# PowerController.net
KiCad netlist of a schematic drawn in EAGLE
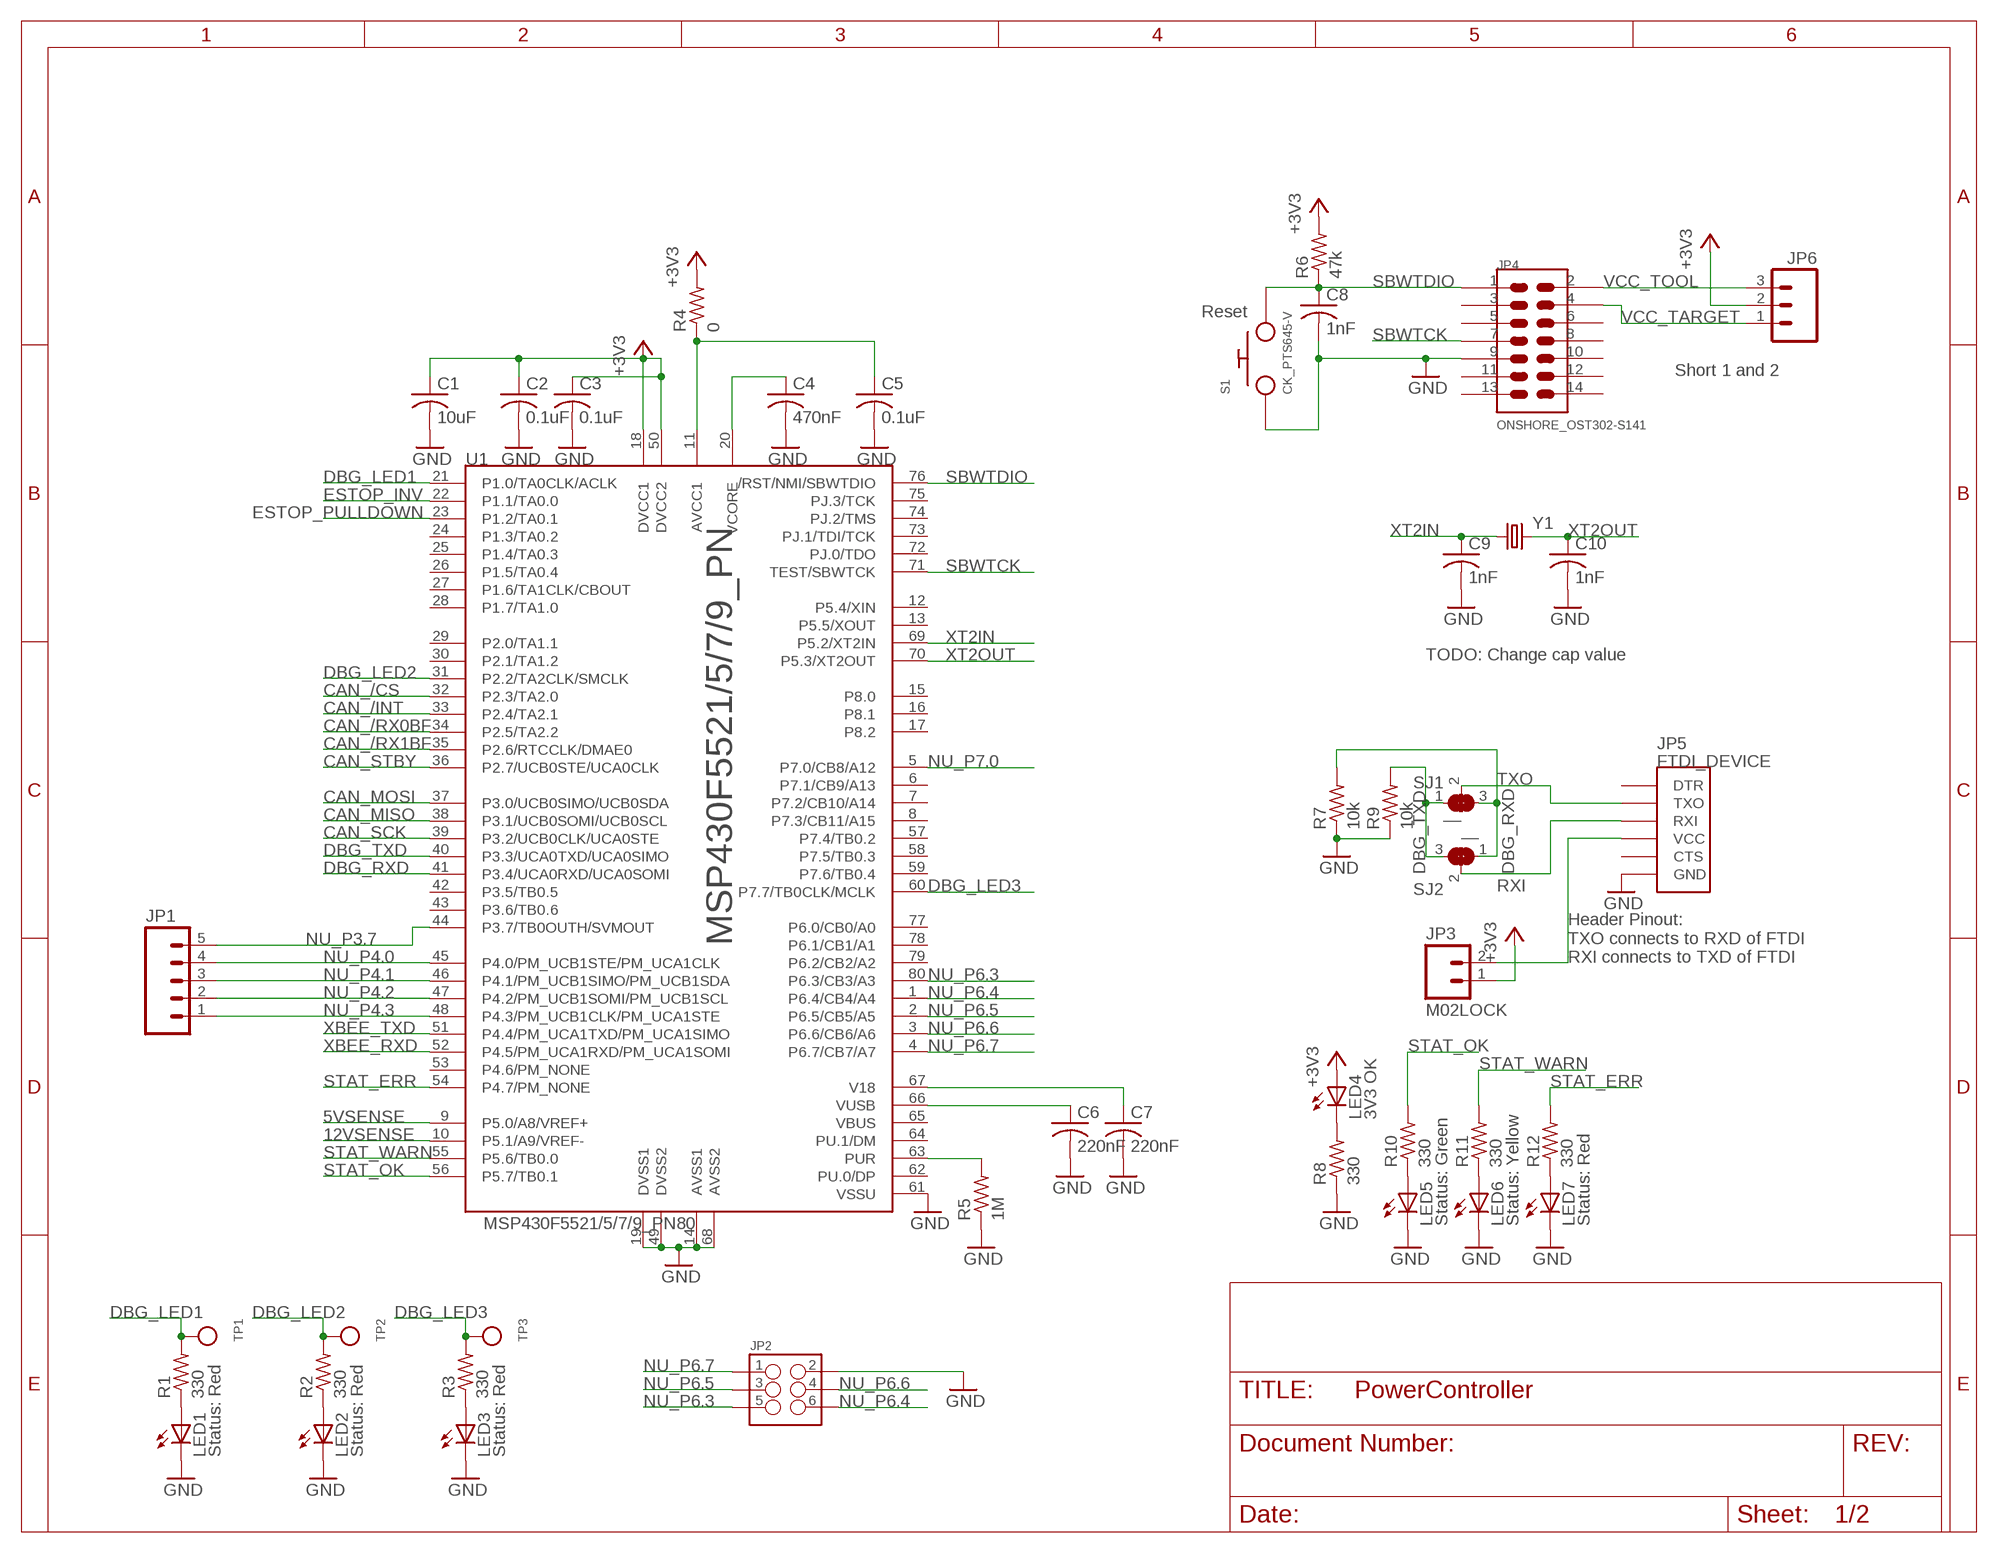
[diagram p0: schematic, sheet 1]
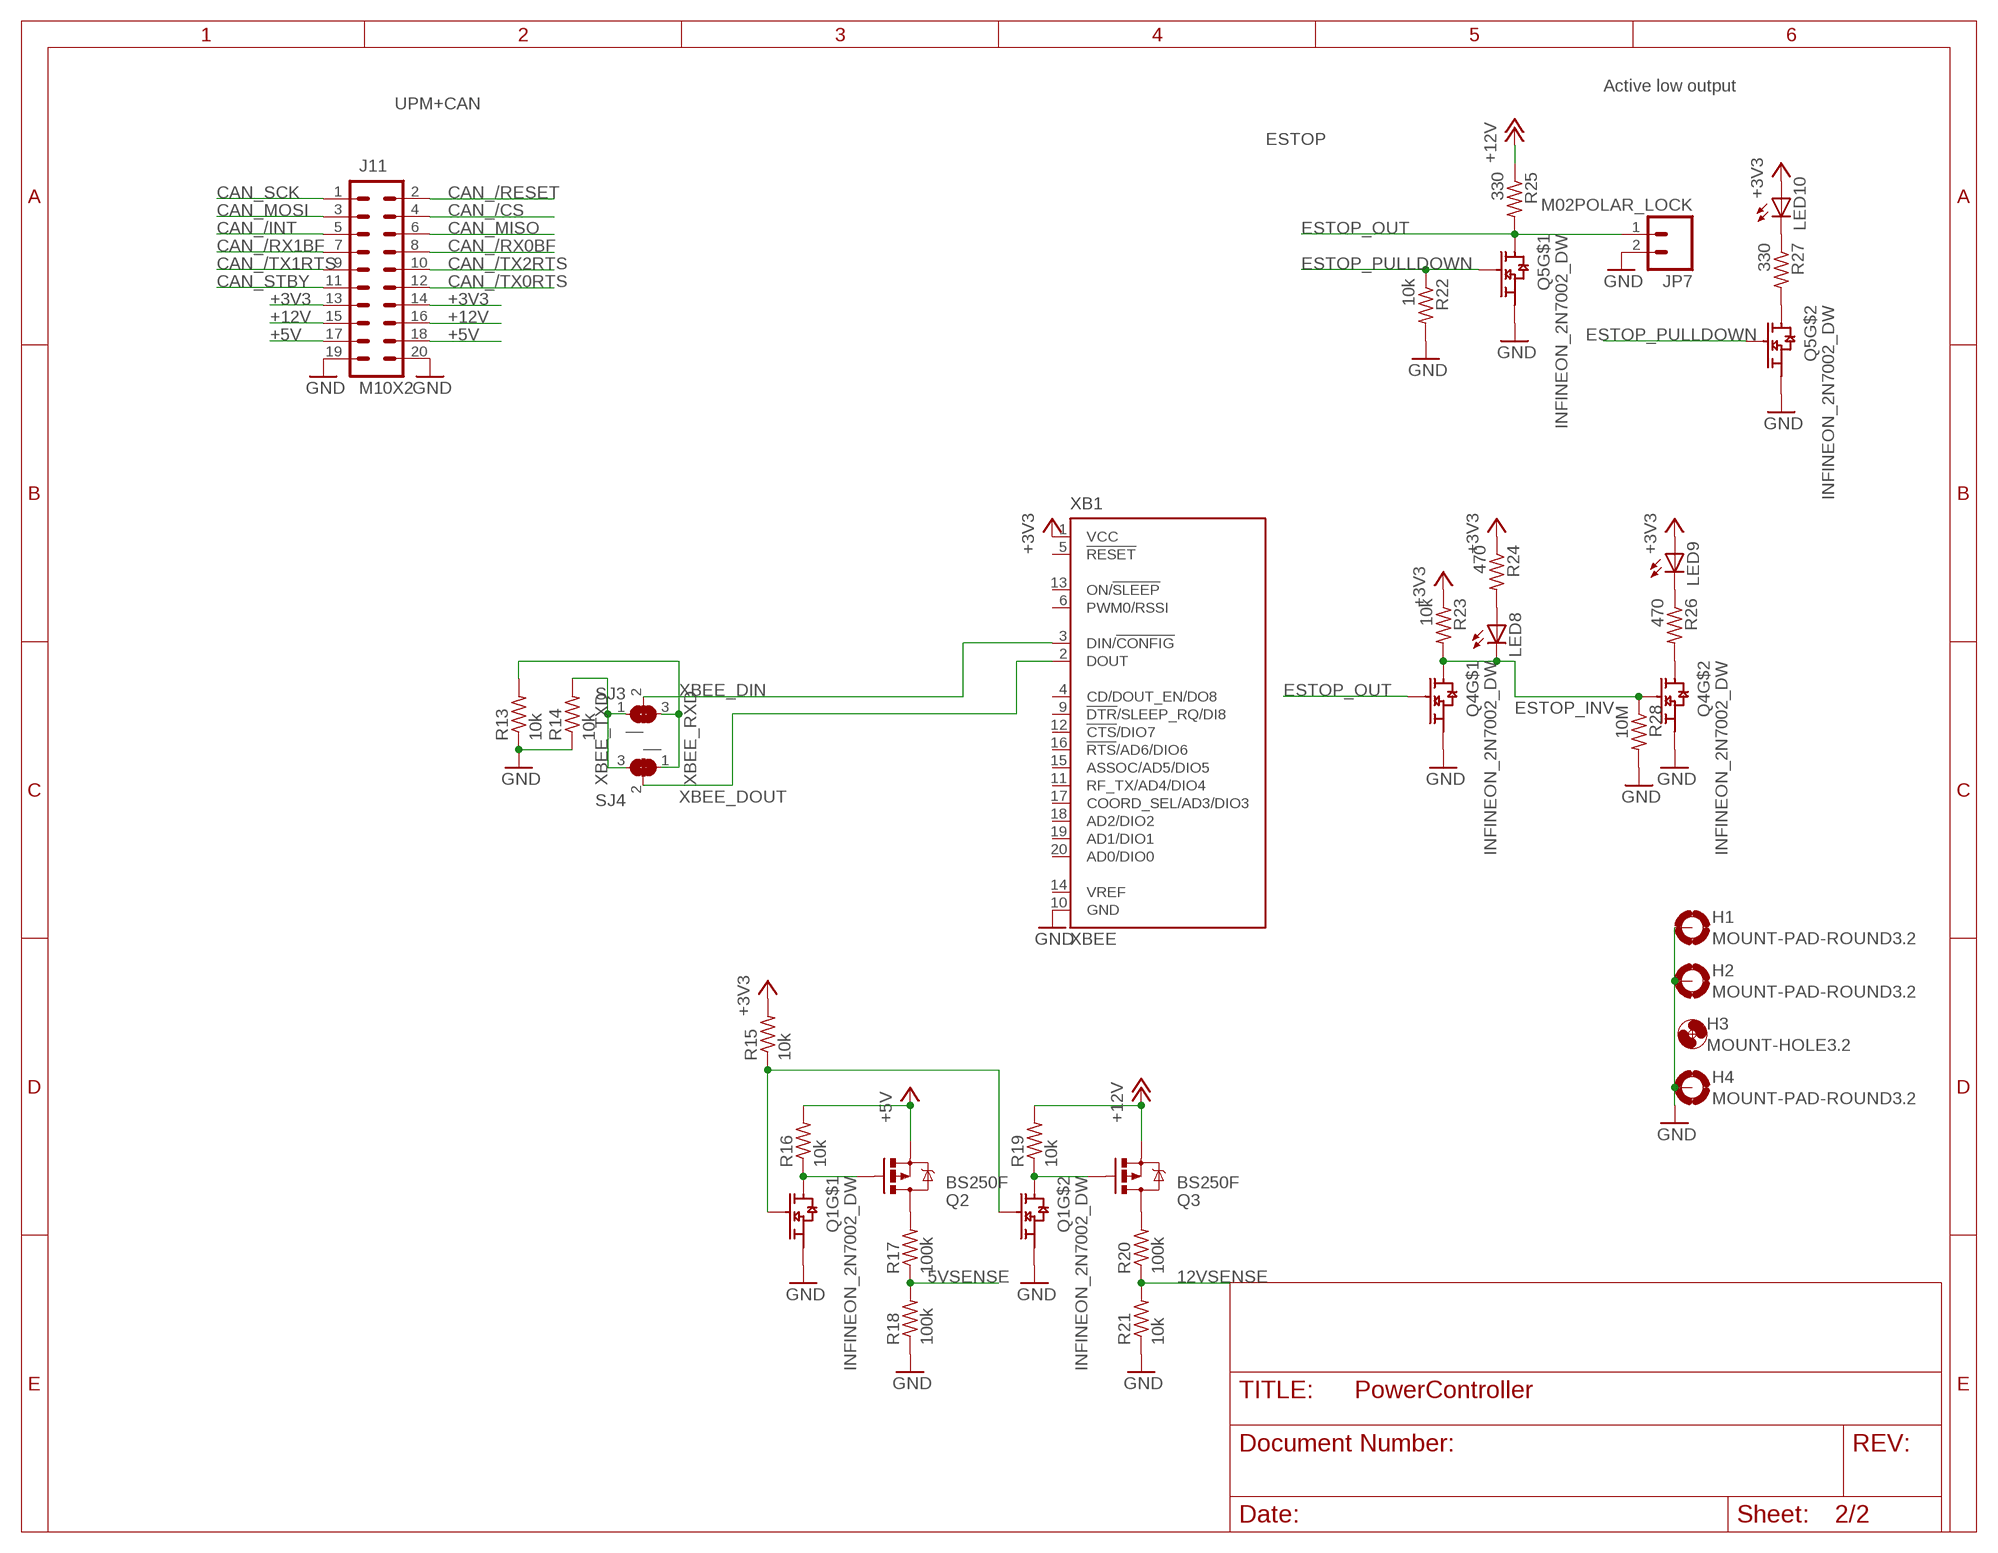
[diagram p1: schematic, sheet 2]

(export (version "E")
  (design (tool "Eeschema 10.0.6"))
  (components
    (comp (ref "H1")
      (value "MOUNT-PAD-ROUND3.2")
      (footprint "eagle-import:3,2-PAD")
      (libsource (lib "eagle-import") (part "MOUNT-PAD-ROUND3.2"))
    )
    (comp (ref "H2")
      (value "MOUNT-PAD-ROUND3.2")
      (footprint "eagle-import:3,2-PAD")
      (libsource (lib "eagle-import") (part "MOUNT-PAD-ROUND3.2"))
    )
    (comp (ref "H3")
      (value "MOUNT-HOLE3.2")
      (footprint "eagle-import:3,2")
      (libsource (lib "eagle-import") (part "MOUNT-HOLE3.2"))
    )
    (comp (ref "H4")
      (value "MOUNT-PAD-ROUND3.2")
      (footprint "eagle-import:3,2-PAD")
      (libsource (lib "eagle-import") (part "MOUNT-PAD-ROUND3.2"))
    )
    (comp (ref "J11")
      (value "M10X2")
      (footprint "eagle-import:2X10")
      (libsource (lib "eagle-import") (part "M10X2"))
    )
    (comp (ref "JP7")
      (value "M02POLAR_LOCK")
      (footprint "eagle-import:MOLEX-1X2_LOCK")
      (libsource (lib "eagle-import") (part "M02POLAR_LOCK"))
    )
    (comp (ref "LED8")
      (value "LED0603")
      (footprint "eagle-import:LED-0603")
      (libsource (lib "eagle-import") (part "LED0603"))
    )
    (comp (ref "LED9")
      (value "LED0603")
      (footprint "eagle-import:LED-0603")
      (libsource (lib "eagle-import") (part "LED0603"))
    )
    (comp (ref "LED10")
      (value "LED0603")
      (footprint "eagle-import:LED-0603")
      (libsource (lib "eagle-import") (part "LED0603"))
    )
    (comp (ref "Q1")
      (value "INFINEON_2N7002_DW")
      (footprint "eagle-import:INFINEON_SOT363")
      (libsource (lib "eagle-import") (part "INFINEON_2N7002_DW"))
    )
    (comp (ref "Q2")
      (value "BS250F")
      (footprint "eagle-import:SOT23-3")
      (libsource (lib "eagle-import") (part "MOSFET-PCHANNELSMD"))
    )
    (comp (ref "Q3")
      (value "BS250F")
      (footprint "eagle-import:SOT23-3")
      (libsource (lib "eagle-import") (part "MOSFET-PCHANNELSMD"))
    )
    (comp (ref "Q4")
      (value "INFINEON_2N7002_DW")
      (footprint "eagle-import:INFINEON_SOT363")
      (libsource (lib "eagle-import") (part "INFINEON_2N7002_DW"))
    )
    (comp (ref "Q5")
      (value "INFINEON_2N7002_DW")
      (footprint "eagle-import:INFINEON_SOT363")
      (libsource (lib "eagle-import") (part "INFINEON_2N7002_DW"))
    )
    (comp (ref "R13")
      (value "10k")
      (footprint "eagle-import:R0603")
      (libsource (lib "eagle-import") (part "R-US_R0603"))
    )
    (comp (ref "R14")
      (value "10k")
      (footprint "eagle-import:R0603")
      (libsource (lib "eagle-import") (part "R-US_R0603"))
    )
    (comp (ref "R15")
      (value "10k")
      (footprint "eagle-import:R0603")
      (libsource (lib "eagle-import") (part "R-US_R0603"))
    )
    (comp (ref "R16")
      (value "10k")
      (footprint "eagle-import:R0603")
      (libsource (lib "eagle-import") (part "R-US_R0603"))
    )
    (comp (ref "R17")
      (value "100k")
      (footprint "eagle-import:R0603")
      (libsource (lib "eagle-import") (part "R-US_R0603"))
    )
    (comp (ref "R18")
      (value "100k")
      (footprint "eagle-import:R0603")
      (libsource (lib "eagle-import") (part "R-US_R0603"))
    )
    (comp (ref "R19")
      (value "10k")
      (footprint "eagle-import:R0603")
      (libsource (lib "eagle-import") (part "R-US_R0603"))
    )
    (comp (ref "R20")
      (value "100k")
      (footprint "eagle-import:R0603")
      (libsource (lib "eagle-import") (part "R-US_R0603"))
    )
    (comp (ref "R21")
      (value "10k")
      (footprint "eagle-import:R0603")
      (libsource (lib "eagle-import") (part "R-US_R0603"))
    )
    (comp (ref "R22")
      (value "10k")
      (footprint "eagle-import:R0603")
      (libsource (lib "eagle-import") (part "R-US_R0603"))
    )
    (comp (ref "R23")
      (value "10k")
      (footprint "eagle-import:R0603")
      (libsource (lib "eagle-import") (part "R-US_R0603"))
    )
    (comp (ref "R24")
      (value "470")
      (footprint "eagle-import:R0603")
      (libsource (lib "eagle-import") (part "R-US_R0603"))
    )
    (comp (ref "R25")
      (value "330")
      (footprint "eagle-import:R0603")
      (libsource (lib "eagle-import") (part "R-US_R0603"))
    )
    (comp (ref "R26")
      (value "470")
      (footprint "eagle-import:R0603")
      (libsource (lib "eagle-import") (part "R-US_R0603"))
    )
    (comp (ref "R27")
      (value "330")
      (footprint "eagle-import:R0603")
      (libsource (lib "eagle-import") (part "R-US_R0603"))
    )
    (comp (ref "R28")
      (value "10M")
      (footprint "eagle-import:R0603")
      (libsource (lib "eagle-import") (part "R-US_R0603"))
    )
    (comp (ref "SJ3")
      (value "SOLDERJUMPER_2WAY0603")
      (footprint "eagle-import:SOLDERJUMPER_2WAY_OPEN_0603")
      (libsource (lib "eagle-import") (part "SOLDERJUMPER_2WAY0603"))
    )
    (comp (ref "SJ4")
      (value "SOLDERJUMPER_2WAY0603")
      (footprint "eagle-import:SOLDERJUMPER_2WAY_OPEN_0603")
      (libsource (lib "eagle-import") (part "SOLDERJUMPER_2WAY0603"))
    )
    (comp (ref "XB1")
      (value "XBEE")
      (footprint "eagle-import:XBEE")
      (libsource (lib "eagle-import") (part "XBEE"))
    )
    (comp (ref "C1")
      (value "10uF")
      (footprint "eagle-import:C0805")
      (libsource (lib "eagle-import") (part "C-USC0805"))
    )
    (comp (ref "C2")
      (value "0.1uF")
      (footprint "eagle-import:C0603")
      (libsource (lib "eagle-import") (part "C-USC0603"))
    )
    (comp (ref "C3")
      (value "0.1uF")
      (footprint "eagle-import:C0603")
      (libsource (lib "eagle-import") (part "C-USC0603"))
    )
    (comp (ref "C4")
      (value "470nF")
      (footprint "eagle-import:C0603")
      (libsource (lib "eagle-import") (part "C-USC0603"))
    )
    (comp (ref "C5")
      (value "0.1uF")
      (footprint "eagle-import:C0603")
      (libsource (lib "eagle-import") (part "C-USC0603"))
    )
    (comp (ref "C6")
      (value "220nF")
      (footprint "eagle-import:C0603")
      (libsource (lib "eagle-import") (part "C-USC0603"))
    )
    (comp (ref "C7")
      (value "220nF")
      (footprint "eagle-import:C0603")
      (libsource (lib "eagle-import") (part "C-USC0603"))
    )
    (comp (ref "C8")
      (value "1nF")
      (footprint "eagle-import:C0603")
      (libsource (lib "eagle-import") (part "C-USC0603"))
    )
    (comp (ref "C9")
      (value "1nF")
      (footprint "eagle-import:C0603")
      (libsource (lib "eagle-import") (part "C-USC0603"))
    )
    (comp (ref "C10")
      (value "1nF")
      (footprint "eagle-import:C0603")
      (libsource (lib "eagle-import") (part "C-USC0603"))
    )
    (comp (ref "JP1")
      (value "M05PTH")
      (footprint "eagle-import:1X05")
      (libsource (lib "eagle-import") (part "M05PTH"))
    )
    (comp (ref "JP2")
      (value "M03X22X3_SILK_SM")
      (footprint "eagle-import:2X3")
      (libsource (lib "eagle-import") (part "M03X22X3_SILK_SM"))
    )
    (comp (ref "JP3")
      (value "M02LOCK")
      (footprint "eagle-import:1X02_LOCK")
      (libsource (lib "eagle-import") (part "M02LOCK"))
    )
    (comp (ref "JP4")
      (value "ONSHORE_OST302-S141")
      (footprint "eagle-import:ONSHORE_OST302-S141")
      (libsource (lib "eagle-import") (part "ONSHORE_OST302-S141"))
    )
    (comp (ref "JP5")
      (value "FTDI_DEVICE")
      (footprint "eagle-import:FTDI_DEVICE_SIDE")
      (libsource (lib "eagle-import") (part "FTDI_DEVICE"))
    )
    (comp (ref "JP6")
      (value "M03LOCK")
      (footprint "eagle-import:1X03_LOCK")
      (libsource (lib "eagle-import") (part "M03LOCK"))
    )
    (comp (ref "LED1")
      (value "Status: Red")
      (footprint "eagle-import:LED-0603")
      (libsource (lib "eagle-import") (part "LED0603"))
    )
    (comp (ref "LED2")
      (value "Status: Red")
      (footprint "eagle-import:LED-0603")
      (libsource (lib "eagle-import") (part "LED0603"))
    )
    (comp (ref "LED3")
      (value "Status: Red")
      (footprint "eagle-import:LED-0603")
      (libsource (lib "eagle-import") (part "LED0603"))
    )
    (comp (ref "LED4")
      (value "3V3 OK")
      (footprint "eagle-import:LED-0603")
      (libsource (lib "eagle-import") (part "LED0603"))
    )
    (comp (ref "LED5")
      (value "Status: Green")
      (footprint "eagle-import:LED-0603")
      (libsource (lib "eagle-import") (part "LED0603"))
    )
    (comp (ref "LED6")
      (value "Status: Yellow")
      (footprint "eagle-import:LED-0603")
      (libsource (lib "eagle-import") (part "LED0603"))
    )
    (comp (ref "LED7")
      (value "Status: Red")
      (footprint "eagle-import:LED-0603")
      (libsource (lib "eagle-import") (part "LED0603"))
    )
    (comp (ref "R1")
      (value "330")
      (footprint "eagle-import:R0603")
      (libsource (lib "eagle-import") (part "R-US_R0603"))
    )
    (comp (ref "R2")
      (value "330")
      (footprint "eagle-import:R0603")
      (libsource (lib "eagle-import") (part "R-US_R0603"))
    )
    (comp (ref "R3")
      (value "330")
      (footprint "eagle-import:R0603")
      (libsource (lib "eagle-import") (part "R-US_R0603"))
    )
    (comp (ref "R4")
      (value "0")
      (footprint "eagle-import:R0603")
      (libsource (lib "eagle-import") (part "R-US_R0603"))
    )
    (comp (ref "R5")
      (value "1M")
      (footprint "eagle-import:R0603")
      (libsource (lib "eagle-import") (part "R-US_R0603"))
    )
    (comp (ref "R6")
      (value "47k")
      (footprint "eagle-import:R0603")
      (libsource (lib "eagle-import") (part "R-US_R0603"))
    )
    (comp (ref "R7")
      (value "10k")
      (footprint "eagle-import:R0603")
      (libsource (lib "eagle-import") (part "R-US_R0603"))
    )
    (comp (ref "R8")
      (value "330")
      (footprint "eagle-import:R0603")
      (libsource (lib "eagle-import") (part "R-US_R0603"))
    )
    (comp (ref "R9")
      (value "10k")
      (footprint "eagle-import:R0603")
      (libsource (lib "eagle-import") (part "R-US_R0603"))
    )
    (comp (ref "R10")
      (value "330")
      (footprint "eagle-import:R0603")
      (libsource (lib "eagle-import") (part "R-US_R0603"))
    )
    (comp (ref "R11")
      (value "330")
      (footprint "eagle-import:R0603")
      (libsource (lib "eagle-import") (part "R-US_R0603"))
    )
    (comp (ref "R12")
      (value "330")
      (footprint "eagle-import:R0603")
      (libsource (lib "eagle-import") (part "R-US_R0603"))
    )
    (comp (ref "S1")
      (value "CK_PTS645-V")
      (footprint "eagle-import:CK_PTS645-V")
      (libsource (lib "eagle-import") (part "CK_PTS645-V"))
    )
    (comp (ref "SJ1")
      (value "SOLDERJUMPER_2WAY0603")
      (footprint "eagle-import:SOLDERJUMPER_2WAY_OPEN_0603")
      (libsource (lib "eagle-import") (part "SOLDERJUMPER_2WAY0603"))
    )
    (comp (ref "SJ2")
      (value "SOLDERJUMPER_2WAY0603")
      (footprint "eagle-import:SOLDERJUMPER_2WAY_OPEN_0603")
      (libsource (lib "eagle-import") (part "SOLDERJUMPER_2WAY0603"))
    )
    (comp (ref "TP1")
      (value "TESTPOINT0.1\"")
      (footprint "eagle-import:1X01_ROUND")
      (libsource (lib "eagle-import") (part "TESTPOINT0.1{dblquote}"))
    )
    (comp (ref "TP2")
      (value "TESTPOINT0.1\"")
      (footprint "eagle-import:1X01_ROUND")
      (libsource (lib "eagle-import") (part "TESTPOINT0.1{dblquote}"))
    )
    (comp (ref "TP3")
      (value "TESTPOINT0.1\"")
      (footprint "eagle-import:1X01_ROUND")
      (libsource (lib "eagle-import") (part "TESTPOINT0.1{dblquote}"))
    )
    (comp (ref "U1")
      (value "MSP430F5521/5/7/9_PN80")
      (footprint "eagle-import:PN80")
      (libsource (lib "eagle-import") (part "MSP430F5521/5/7/9_PN80"))
    )
    (comp (ref "Y1")
      (value "CRYSTALHC49UV")
      (footprint "eagle-import:HC49U-V")
      (libsource (lib "eagle-import") (part "CRYSTALHC49UV"))
    )
  )
  (nets
    (net (code "1") (name "+3V3") (class "Default")
      (node (ref "C1") (pin "1") (pinfunction "1_1") (pintype "passive"))
      (node (ref "C2") (pin "1") (pinfunction "1_1") (pintype "passive"))
      (node (ref "C3") (pin "1") (pinfunction "1_1") (pintype "passive"))
      (node (ref "J11") (pin "13") (pinfunction "13_13") (pintype "passive"))
      (node (ref "J11") (pin "14") (pinfunction "14_14") (pintype "passive"))
      (node (ref "JP3") (pin "1") (pinfunction "1_1") (pintype "passive"))
      (node (ref "JP6") (pin "2") (pinfunction "2_2") (pintype "passive"))
      (node (ref "LED10") (pin "A") (pinfunction "A_A") (pintype "passive"))
      (node (ref "LED4") (pin "A") (pinfunction "A_A") (pintype "passive"))
      (node (ref "LED9") (pin "A") (pinfunction "A_A") (pintype "passive"))
      (node (ref "R15") (pin "2") (pinfunction "2_2") (pintype "passive"))
      (node (ref "R23") (pin "1") (pinfunction "1_1") (pintype "passive"))
      (node (ref "R24") (pin "1") (pinfunction "1_1") (pintype "passive"))
      (node (ref "R4") (pin "2") (pinfunction "2_2") (pintype "passive"))
      (node (ref "R6") (pin "2") (pinfunction "2_2") (pintype "passive"))
      (node (ref "U1") (pin "18") (pinfunction "DVCC1_18") (pintype "bidirectional"))
      (node (ref "U1") (pin "50") (pinfunction "DVCC2_50") (pintype "bidirectional"))
      (node (ref "XB1") (pin "1") (pinfunction "VCC_1") (pintype "power_in"))
    )
    (net (code "2") (name "+5V") (class "Default")
      (node (ref "J11") (pin "17") (pinfunction "17_17") (pintype "passive"))
      (node (ref "J11") (pin "18") (pinfunction "18_18") (pintype "passive"))
      (node (ref "Q2") (pin "2") (pinfunction "S_2") (pintype "passive"))
      (node (ref "R16") (pin "2") (pinfunction "2_2") (pintype "passive"))
    )
    (net (code "3") (name "+12V") (class "Default")
      (node (ref "J11") (pin "15") (pinfunction "15_15") (pintype "passive"))
      (node (ref "J11") (pin "16") (pinfunction "16_16") (pintype "passive"))
      (node (ref "Q3") (pin "2") (pinfunction "S_2") (pintype "passive"))
      (node (ref "R19") (pin "2") (pinfunction "2_2") (pintype "passive"))
      (node (ref "R25") (pin "1") (pinfunction "1_1") (pintype "passive"))
    )
    (net (code "4") (name "5VSENSE") (class "Default")
      (node (ref "R17") (pin "1") (pinfunction "1_1") (pintype "passive"))
      (node (ref "R18") (pin "2") (pinfunction "2_2") (pintype "passive"))
      (node (ref "U1") (pin "9") (pinfunction "P5.0/A8/VREF+_9") (pintype "bidirectional"))
    )
    (net (code "5") (name "12VSENSE") (class "Default")
      (node (ref "R20") (pin "1") (pinfunction "1_1") (pintype "passive"))
      (node (ref "R21") (pin "2") (pinfunction "2_2") (pintype "passive"))
      (node (ref "U1") (pin "10") (pinfunction "P5.1/A9/VREF-_10") (pintype "bidirectional"))
    )
    (net (code "6") (name "CAN_MISO") (class "Default")
      (node (ref "J11") (pin "6") (pinfunction "6_6") (pintype "passive"))
      (node (ref "U1") (pin "38") (pinfunction "P3.1/UCB0SOMI/UCB0SCL_38") (pintype "bidirectional"))
    )
    (net (code "7") (name "CAN_MOSI") (class "Default")
      (node (ref "J11") (pin "3") (pinfunction "3_3") (pintype "passive"))
      (node (ref "U1") (pin "37") (pinfunction "P3.0/UCB0SIMO/UCB0SDA_37") (pintype "bidirectional"))
    )
    (net (code "8") (name "CAN_SCK") (class "Default")
      (node (ref "J11") (pin "1") (pinfunction "1_1") (pintype "passive"))
      (node (ref "U1") (pin "39") (pinfunction "P3.2/UCB0CLK/UCA0STE_39") (pintype "bidirectional"))
    )
    (net (code "9") (name "CAN_STBY") (class "Default")
      (node (ref "J11") (pin "11") (pinfunction "11_11") (pintype "passive"))
      (node (ref "U1") (pin "36") (pinfunction "P2.7/UCB0STE/UCA0CLK_36") (pintype "bidirectional"))
    )
    (net (code "10") (name "CAN_{slash}CS") (class "Default")
      (node (ref "J11") (pin "4") (pinfunction "4_4") (pintype "passive"))
      (node (ref "U1") (pin "32") (pinfunction "P2.3/TA2.0_32") (pintype "bidirectional"))
    )
    (net (code "11") (name "CAN_{slash}INT") (class "Default")
      (node (ref "J11") (pin "5") (pinfunction "5_5") (pintype "passive"))
      (node (ref "U1") (pin "33") (pinfunction "P2.4/TA2.1_33") (pintype "bidirectional"))
    )
    (net (code "12") (name "CAN_{slash}RESET") (class "Default")
      (node (ref "J11") (pin "2") (pinfunction "2_2") (pintype "passive"))
    )
    (net (code "13") (name "CAN_{slash}RX0BF") (class "Default")
      (node (ref "J11") (pin "8") (pinfunction "8_8") (pintype "passive"))
      (node (ref "U1") (pin "34") (pinfunction "P2.5/TA2.2_34") (pintype "bidirectional"))
    )
    (net (code "14") (name "CAN_{slash}RX1BF") (class "Default")
      (node (ref "J11") (pin "7") (pinfunction "7_7") (pintype "passive"))
      (node (ref "U1") (pin "35") (pinfunction "P2.6/RTCCLK/DMAE0_35") (pintype "bidirectional"))
    )
    (net (code "15") (name "CAN_{slash}TX0RTS") (class "Default")
      (node (ref "J11") (pin "12") (pinfunction "12_12") (pintype "passive"))
    )
    (net (code "16") (name "CAN_{slash}TX1RTS") (class "Default")
      (node (ref "J11") (pin "9") (pinfunction "9_9") (pintype "passive"))
    )
    (net (code "17") (name "CAN_{slash}TX2RTS") (class "Default")
      (node (ref "J11") (pin "10") (pinfunction "10_10") (pintype "passive"))
    )
    (net (code "18") (name "DBG_LED1") (class "Default")
      (node (ref "R1") (pin "2") (pinfunction "2_2") (pintype "passive"))
      (node (ref "TP1") (pin "1") (pinfunction "P$1_1") (pintype "bidirectional"))
      (node (ref "U1") (pin "21") (pinfunction "P1.0/TA0CLK/ACLK_21") (pintype "bidirectional"))
    )
    (net (code "19") (name "DBG_LED2") (class "Default")
      (node (ref "R2") (pin "2") (pinfunction "2_2") (pintype "passive"))
      (node (ref "TP2") (pin "1") (pinfunction "P$1_1") (pintype "bidirectional"))
      (node (ref "U1") (pin "31") (pinfunction "P2.2/TA2CLK/SMCLK_31") (pintype "bidirectional"))
    )
    (net (code "20") (name "DBG_LED3") (class "Default")
      (node (ref "R3") (pin "2") (pinfunction "2_2") (pintype "passive"))
      (node (ref "TP3") (pin "1") (pinfunction "P$1_1") (pintype "bidirectional"))
      (node (ref "U1") (pin "60") (pinfunction "P7.7/TB0CLK/MCLK_60") (pintype "bidirectional"))
    )
    (net (code "21") (name "DBG_RXD") (class "Default")
      (node (ref "R7") (pin "2") (pinfunction "2_2") (pintype "passive"))
      (node (ref "SJ1") (pin "3") (pinfunction "3_3") (pintype "passive"))
      (node (ref "SJ2") (pin "1") (pinfunction "1_1") (pintype "passive"))
      (node (ref "U1") (pin "41") (pinfunction "P3.4/UCA0RXD/UCA0SOMI_41") (pintype "bidirectional"))
    )
    (net (code "22") (name "DBG_TXD") (class "Default")
      (node (ref "R9") (pin "2") (pinfunction "2_2") (pintype "passive"))
      (node (ref "SJ1") (pin "1") (pinfunction "1_1") (pintype "passive"))
      (node (ref "SJ2") (pin "3") (pinfunction "3_3") (pintype "passive"))
      (node (ref "U1") (pin "40") (pinfunction "P3.3/UCA0TXD/UCA0SIMO_40") (pintype "bidirectional"))
    )
    (net (code "23") (name "ESTOP_INV") (class "Default")
      (node (ref "LED8") (pin "C") (pinfunction "C_C") (pintype "passive"))
      (node (ref "Q4") (pin "5") (pinfunction "GATE_5") (pintype "bidirectional"))
      (node (ref "Q4") (pin "6") (pinfunction "DRAIN_6") (pintype "bidirectional"))
      (node (ref "R23") (pin "2") (pinfunction "2_2") (pintype "passive"))
      (node (ref "R28") (pin "1") (pinfunction "1_1") (pintype "passive"))
      (node (ref "U1") (pin "22") (pinfunction "P1.1/TA0.0_22") (pintype "bidirectional"))
    )
    (net (code "24") (name "ESTOP_OUT") (class "Default")
      (node (ref "JP7") (pin "1") (pinfunction "1_1") (pintype "passive"))
      (node (ref "Q4") (pin "2") (pinfunction "GATE_2") (pintype "bidirectional"))
      (node (ref "Q5") (pin "6") (pinfunction "DRAIN_6") (pintype "bidirectional"))
      (node (ref "R25") (pin "2") (pinfunction "2_2") (pintype "passive"))
    )
    (net (code "25") (name "ESTOP_PULLDOWN") (class "Default")
      (node (ref "Q5") (pin "2") (pinfunction "GATE_2") (pintype "bidirectional"))
      (node (ref "Q5") (pin "5") (pinfunction "GATE_5") (pintype "bidirectional"))
      (node (ref "R22") (pin "1") (pinfunction "1_1") (pintype "passive"))
      (node (ref "U1") (pin "23") (pinfunction "P1.2/TA0.1_23") (pintype "bidirectional"))
    )
    (net (code "26") (name "GND") (class "Default")
      (node (ref "C1") (pin "2") (pinfunction "2_2") (pintype "passive"))
      (node (ref "C10") (pin "2") (pinfunction "2_2") (pintype "passive"))
      (node (ref "C2") (pin "2") (pinfunction "2_2") (pintype "passive"))
      (node (ref "C3") (pin "2") (pinfunction "2_2") (pintype "passive"))
      (node (ref "C4") (pin "2") (pinfunction "2_2") (pintype "passive"))
      (node (ref "C5") (pin "2") (pinfunction "2_2") (pintype "passive"))
      (node (ref "C6") (pin "2") (pinfunction "2_2") (pintype "passive"))
      (node (ref "C7") (pin "2") (pinfunction "2_2") (pintype "passive"))
      (node (ref "C8") (pin "2") (pinfunction "2_2") (pintype "passive"))
      (node (ref "C9") (pin "2") (pinfunction "2_2") (pintype "passive"))
      (node (ref "H1") (pin "B3,2") (pinfunction "MOUNT_B3,2") (pintype "passive"))
      (node (ref "H2") (pin "B3,2") (pinfunction "MOUNT_B3,2") (pintype "passive"))
      (node (ref "H4") (pin "B3,2") (pinfunction "MOUNT_B3,2") (pintype "passive"))
      (node (ref "J11") (pin "19") (pinfunction "19_19") (pintype "passive"))
      (node (ref "J11") (pin "20") (pinfunction "20_20") (pintype "passive"))
      (node (ref "JP2") (pin "2") (pinfunction "2_2") (pintype "bidirectional"))
      (node (ref "JP4") (pin "9") (pinfunction "9_9") (pintype "bidirectional"))
      (node (ref "JP5") (pin "P$6") (pinfunction "GND_P$6") (pintype "bidirectional"))
      (node (ref "JP7") (pin "2") (pinfunction "2_2") (pintype "passive"))
      (node (ref "LED1") (pin "C") (pinfunction "C_C") (pintype "passive"))
      (node (ref "LED2") (pin "C") (pinfunction "C_C") (pintype "passive"))
      (node (ref "LED3") (pin "C") (pinfunction "C_C") (pintype "passive"))
      (node (ref "LED5") (pin "C") (pinfunction "C_C") (pintype "passive"))
      (node (ref "LED6") (pin "C") (pinfunction "C_C") (pintype "passive"))
      (node (ref "LED7") (pin "C") (pinfunction "C_C") (pintype "passive"))
      (node (ref "Q1") (pin "1") (pinfunction "SOURCE_1") (pintype "bidirectional"))
      (node (ref "Q1") (pin "4") (pinfunction "SOURCE_4") (pintype "bidirectional"))
      (node (ref "Q4") (pin "1") (pinfunction "SOURCE_1") (pintype "bidirectional"))
      (node (ref "Q4") (pin "4") (pinfunction "SOURCE_4") (pintype "bidirectional"))
      (node (ref "Q5") (pin "1") (pinfunction "SOURCE_1") (pintype "bidirectional"))
      (node (ref "Q5") (pin "4") (pinfunction "SOURCE_4") (pintype "bidirectional"))
      (node (ref "R13") (pin "1") (pinfunction "1_1") (pintype "passive"))
      (node (ref "R14") (pin "1") (pinfunction "1_1") (pintype "passive"))
      (node (ref "R18") (pin "1") (pinfunction "1_1") (pintype "passive"))
      (node (ref "R21") (pin "1") (pinfunction "1_1") (pintype "passive"))
      (node (ref "R22") (pin "2") (pinfunction "2_2") (pintype "passive"))
      (node (ref "R28") (pin "2") (pinfunction "2_2") (pintype "passive"))
      (node (ref "R5") (pin "1") (pinfunction "1_1") (pintype "passive"))
      (node (ref "R7") (pin "1") (pinfunction "1_1") (pintype "passive"))
      (node (ref "R8") (pin "1") (pinfunction "1_1") (pintype "passive"))
      (node (ref "R9") (pin "1") (pinfunction "1_1") (pintype "passive"))
      (node (ref "S1") (pin "1") (pinfunction "1_1") (pintype "bidirectional"))
      (node (ref "U1") (pin "14") (pinfunction "AVSS1_14") (pintype "bidirectional"))
      (node (ref "U1") (pin "19") (pinfunction "DVSS1_19") (pintype "bidirectional"))
      (node (ref "U1") (pin "49") (pinfunction "DVSS2_49") (pintype "bidirectional"))
      (node (ref "U1") (pin "61") (pinfunction "VSSU_61") (pintype "bidirectional"))
      (node (ref "U1") (pin "68") (pinfunction "AVSS2_68") (pintype "bidirectional"))
      (node (ref "XB1") (pin "10") (pinfunction "GND_10") (pintype "power_in"))
    )
    (net (code "27") (name "NU_P3.7") (class "Default")
      (node (ref "JP1") (pin "5") (pinfunction "5_5") (pintype "passive"))
      (node (ref "U1") (pin "44") (pinfunction "P3.7/TB0OUTH/SVMOUT_44") (pintype "bidirectional"))
    )
    (net (code "28") (name "NU_P4.0") (class "Default")
      (node (ref "JP1") (pin "4") (pinfunction "4_4") (pintype "passive"))
      (node (ref "U1") (pin "45") (pinfunction "P4.0/PM_UCB1STE/PM_UCA1CLK_45") (pintype "bidirectional"))
    )
    (net (code "29") (name "NU_P4.1") (class "Default")
      (node (ref "JP1") (pin "3") (pinfunction "3_3") (pintype "passive"))
      (node (ref "U1") (pin "46") (pinfunction "P4.1/PM_UCB1SIMO/PM_UCB1SDA_46") (pintype "bidirectional"))
    )
    (net (code "30") (name "NU_P4.2") (class "Default")
      (node (ref "JP1") (pin "2") (pinfunction "2_2") (pintype "passive"))
      (node (ref "U1") (pin "47") (pinfunction "P4.2/PM_UCB1SOMI/PM_UCB1SCL_47") (pintype "bidirectional"))
    )
    (net (code "31") (name "NU_P4.3") (class "Default")
      (node (ref "JP1") (pin "1") (pinfunction "1_1") (pintype "passive"))
      (node (ref "U1") (pin "48") (pinfunction "P4.3/PM_UCB1CLK/PM_UCA1STE_48") (pintype "bidirectional"))
    )
    (net (code "32") (name "NU_P6.3") (class "Default")
      (node (ref "JP2") (pin "5") (pinfunction "5_5") (pintype "bidirectional"))
      (node (ref "U1") (pin "80") (pinfunction "P6.3/CB3/A3_80") (pintype "bidirectional"))
    )
    (net (code "33") (name "NU_P6.4") (class "Default")
      (node (ref "JP2") (pin "6") (pinfunction "6_6") (pintype "bidirectional"))
      (node (ref "U1") (pin "1") (pinfunction "P6.4/CB4/A4_1") (pintype "bidirectional"))
    )
    (net (code "34") (name "NU_P6.5") (class "Default")
      (node (ref "JP2") (pin "3") (pinfunction "3_3") (pintype "bidirectional"))
      (node (ref "U1") (pin "2") (pinfunction "P6.5/CB5/A5_2") (pintype "bidirectional"))
    )
    (net (code "35") (name "NU_P6.6") (class "Default")
      (node (ref "JP2") (pin "4") (pinfunction "4_4") (pintype "bidirectional"))
      (node (ref "U1") (pin "3") (pinfunction "P6.6/CB6/A6_3") (pintype "bidirectional"))
    )
    (net (code "36") (name "NU_P6.7") (class "Default")
      (node (ref "JP2") (pin "1") (pinfunction "1_1") (pintype "bidirectional"))
      (node (ref "U1") (pin "4") (pinfunction "P6.7/CB7/A7_4") (pintype "bidirectional"))
    )
    (net (code "37") (name "NU_P7.0") (class "Default")
      (node (ref "U1") (pin "5") (pinfunction "P7.0/CB8/A12_5") (pintype "bidirectional"))
    )
    (net (code "38") (name "Net-(JP5-VCC)") (class "Default")
      (node (ref "JP3") (pin "2") (pinfunction "2_2") (pintype "passive"))
      (node (ref "JP5") (pin "P$4") (pinfunction "VCC_P$4") (pintype "bidirectional"))
    )
    (net (code "39") (name "Net-(LED1-PadA)") (class "Default")
      (node (ref "LED1") (pin "A") (pinfunction "A_A") (pintype "passive"))
      (node (ref "R1") (pin "1") (pinfunction "1_1") (pintype "passive"))
    )
    (net (code "40") (name "Net-(LED2-PadA)") (class "Default")
      (node (ref "LED2") (pin "A") (pinfunction "A_A") (pintype "passive"))
      (node (ref "R2") (pin "1") (pinfunction "1_1") (pintype "passive"))
    )
    (net (code "41") (name "Net-(LED3-PadA)") (class "Default")
      (node (ref "LED3") (pin "A") (pinfunction "A_A") (pintype "passive"))
      (node (ref "R3") (pin "1") (pinfunction "1_1") (pintype "passive"))
    )
    (net (code "42") (name "Net-(LED4-PadC)") (class "Default")
      (node (ref "LED4") (pin "C") (pinfunction "C_C") (pintype "passive"))
      (node (ref "R8") (pin "2") (pinfunction "2_2") (pintype "passive"))
    )
    (net (code "43") (name "Net-(LED5-PadA)") (class "Default")
      (node (ref "LED5") (pin "A") (pinfunction "A_A") (pintype "passive"))
      (node (ref "R10") (pin "1") (pinfunction "1_1") (pintype "passive"))
    )
    (net (code "44") (name "Net-(LED6-PadA)") (class "Default")
      (node (ref "LED6") (pin "A") (pinfunction "A_A") (pintype "passive"))
      (node (ref "R11") (pin "1") (pinfunction "1_1") (pintype "passive"))
    )
    (net (code "45") (name "Net-(LED7-PadA)") (class "Default")
      (node (ref "LED7") (pin "A") (pinfunction "A_A") (pintype "passive"))
      (node (ref "R12") (pin "1") (pinfunction "1_1") (pintype "passive"))
    )
    (net (code "46") (name "Net-(LED8-PadA)") (class "Default")
      (node (ref "LED8") (pin "A") (pinfunction "A_A") (pintype "passive"))
      (node (ref "R24") (pin "2") (pinfunction "2_2") (pintype "passive"))
    )
    (net (code "47") (name "Net-(LED9-PadC)") (class "Default")
      (node (ref "LED9") (pin "C") (pinfunction "C_C") (pintype "passive"))
      (node (ref "R26") (pin "1") (pinfunction "1_1") (pintype "passive"))
    )
    (net (code "48") (name "Net-(LED10-PadC)") (class "Default")
      (node (ref "LED10") (pin "C") (pinfunction "C_C") (pintype "passive"))
      (node (ref "R27") (pin "1") (pinfunction "1_1") (pintype "passive"))
    )
    (net (code "49") (name "Net-(Q1A-DRAIN)") (class "Default")
      (node (ref "Q1") (pin "6") (pinfunction "DRAIN_6") (pintype "bidirectional"))
      (node (ref "Q2") (pin "1") (pinfunction "G_1") (pintype "passive"))
      (node (ref "R16") (pin "1") (pinfunction "1_1") (pintype "passive"))
    )
    (net (code "50") (name "Net-(Q1A-GATE)") (class "Default")
      (node (ref "Q1") (pin "2") (pinfunction "GATE_2") (pintype "bidirectional"))
      (node (ref "Q1") (pin "5") (pinfunction "GATE_5") (pintype "bidirectional"))
      (node (ref "R15") (pin "1") (pinfunction "1_1") (pintype "passive"))
    )
    (net (code "51") (name "Net-(Q1B-DRAIN)") (class "Default")
      (node (ref "Q1") (pin "3") (pinfunction "DRAIN_3") (pintype "bidirectional"))
      (node (ref "Q3") (pin "1") (pinfunction "G_1") (pintype "passive"))
      (node (ref "R19") (pin "1") (pinfunction "1_1") (pintype "passive"))
    )
    (net (code "52") (name "Net-(Q2-D)") (class "Default")
      (node (ref "Q2") (pin "3") (pinfunction "D_3") (pintype "passive"))
      (node (ref "R17") (pin "2") (pinfunction "2_2") (pintype "passive"))
    )
    (net (code "53") (name "Net-(Q3-D)") (class "Default")
      (node (ref "Q3") (pin "3") (pinfunction "D_3") (pintype "passive"))
      (node (ref "R20") (pin "2") (pinfunction "2_2") (pintype "passive"))
    )
    (net (code "54") (name "Net-(Q4B-DRAIN)") (class "Default")
      (node (ref "Q4") (pin "3") (pinfunction "DRAIN_3") (pintype "bidirectional"))
      (node (ref "R26") (pin "2") (pinfunction "2_2") (pintype "passive"))
    )
    (net (code "55") (name "Net-(Q5B-DRAIN)") (class "Default")
      (node (ref "Q5") (pin "3") (pinfunction "DRAIN_3") (pintype "bidirectional"))
      (node (ref "R27") (pin "2") (pinfunction "2_2") (pintype "passive"))
    )
    (net (code "56") (name "Net-(U1-AVCC1)") (class "Default")
      (node (ref "C5") (pin "1") (pinfunction "1_1") (pintype "passive"))
      (node (ref "R4") (pin "1") (pinfunction "1_1") (pintype "passive"))
      (node (ref "U1") (pin "11") (pinfunction "AVCC1_11") (pintype "bidirectional"))
    )
    (net (code "57") (name "Net-(U1-PUR)") (class "Default")
      (node (ref "R5") (pin "2") (pinfunction "2_2") (pintype "passive"))
      (node (ref "U1") (pin "63") (pinfunction "PUR_63") (pintype "bidirectional"))
    )
    (net (code "58") (name "Net-(U1-V18)") (class "Default")
      (node (ref "C7") (pin "1") (pinfunction "1_1") (pintype "passive"))
      (node (ref "U1") (pin "67") (pinfunction "V18_67") (pintype "bidirectional"))
    )
    (net (code "59") (name "Net-(U1-VCORE)") (class "Default")
      (node (ref "C4") (pin "1") (pinfunction "1_1") (pintype "passive"))
      (node (ref "U1") (pin "20") (pinfunction "VCORE_20") (pintype "bidirectional"))
    )
    (net (code "60") (name "Net-(U1-VUSB)") (class "Default")
      (node (ref "C6") (pin "1") (pinfunction "1_1") (pintype "passive"))
      (node (ref "U1") (pin "66") (pinfunction "VUSB_66") (pintype "bidirectional"))
    )
    (net (code "61") (name "RXI") (class "Default")
      (node (ref "JP5") (pin "P$3") (pinfunction "RXI_P$3") (pintype "bidirectional"))
      (node (ref "SJ2") (pin "2") (pinfunction "2_2") (pintype "passive"))
    )
    (net (code "62") (name "SBWTCK") (class "Default")
      (node (ref "JP4") (pin "7") (pinfunction "7_7") (pintype "bidirectional"))
      (node (ref "U1") (pin "71") (pinfunction "TEST/SBWTCK_71") (pintype "bidirectional"))
    )
    (net (code "63") (name "SBWTDIO") (class "Default")
      (node (ref "C8") (pin "1") (pinfunction "1_1") (pintype "passive"))
      (node (ref "JP4") (pin "1") (pinfunction "1_1") (pintype "bidirectional"))
      (node (ref "R6") (pin "1") (pinfunction "1_1") (pintype "passive"))
      (node (ref "S1") (pin "2") (pinfunction "2_2") (pintype "bidirectional"))
      (node (ref "U1") (pin "76") (pinfunction "/RST/NMI/SBWTDIO_76") (pintype "bidirectional"))
    )
    (net (code "64") (name "STAT_ERR") (class "Default")
      (node (ref "R12") (pin "2") (pinfunction "2_2") (pintype "passive"))
      (node (ref "U1") (pin "54") (pinfunction "P4.7/PM_NONE_54") (pintype "bidirectional"))
    )
    (net (code "65") (name "STAT_OK") (class "Default")
      (node (ref "R10") (pin "2") (pinfunction "2_2") (pintype "passive"))
      (node (ref "U1") (pin "56") (pinfunction "P5.7/TB0.1_56") (pintype "bidirectional"))
    )
    (net (code "66") (name "STAT_WARN") (class "Default")
      (node (ref "R11") (pin "2") (pinfunction "2_2") (pintype "passive"))
      (node (ref "U1") (pin "55") (pinfunction "P5.6/TB0.0_55") (pintype "bidirectional"))
    )
    (net (code "67") (name "TXO") (class "Default")
      (node (ref "JP5") (pin "P$2") (pinfunction "TXO_P$2") (pintype "bidirectional"))
      (node (ref "SJ1") (pin "2") (pinfunction "2_2") (pintype "passive"))
    )
    (net (code "68") (name "VCC_TARGET") (class "Default")
      (node (ref "JP4") (pin "4") (pinfunction "4_4") (pintype "bidirectional"))
      (node (ref "JP6") (pin "1") (pinfunction "1_1") (pintype "passive"))
    )
    (net (code "69") (name "VCC_TOOL") (class "Default")
      (node (ref "JP4") (pin "2") (pinfunction "2_2") (pintype "bidirectional"))
      (node (ref "JP6") (pin "3") (pinfunction "3_3") (pintype "passive"))
    )
    (net (code "70") (name "XBEE_DIN") (class "Default")
      (node (ref "SJ3") (pin "2") (pinfunction "2_2") (pintype "passive"))
      (node (ref "XB1") (pin "3") (pinfunction "DIN/~{CONFIG}_3") (pintype "input"))
    )
    (net (code "71") (name "XBEE_DOUT") (class "Default")
      (node (ref "SJ4") (pin "2") (pinfunction "2_2") (pintype "passive"))
      (node (ref "XB1") (pin "2") (pinfunction "DOUT_2") (pintype "output"))
    )
    (net (code "72") (name "XBEE_RXD") (class "Default")
      (node (ref "R13") (pin "2") (pinfunction "2_2") (pintype "passive"))
      (node (ref "SJ3") (pin "3") (pinfunction "3_3") (pintype "passive"))
      (node (ref "SJ4") (pin "1") (pinfunction "1_1") (pintype "passive"))
      (node (ref "U1") (pin "52") (pinfunction "P4.5/PM_UCA1RXD/PM_UCA1SOMI_52") (pintype "bidirectional"))
    )
    (net (code "73") (name "XBEE_TXD") (class "Default")
      (node (ref "R14") (pin "2") (pinfunction "2_2") (pintype "passive"))
      (node (ref "SJ3") (pin "1") (pinfunction "1_1") (pintype "passive"))
      (node (ref "SJ4") (pin "3") (pinfunction "3_3") (pintype "passive"))
      (node (ref "U1") (pin "51") (pinfunction "P4.4/PM_UCA1TXD/PM_UCA1SIMO_51") (pintype "bidirectional"))
    )
    (net (code "74") (name "XT2IN") (class "Default")
      (node (ref "C9") (pin "1") (pinfunction "1_1") (pintype "passive"))
      (node (ref "U1") (pin "69") (pinfunction "P5.2/XT2IN_69") (pintype "bidirectional"))
      (node (ref "Y1") (pin "1") (pinfunction "1_1") (pintype "passive"))
    )
    (net (code "75") (name "XT2OUT") (class "Default")
      (node (ref "C10") (pin "1") (pinfunction "1_1") (pintype "passive"))
      (node (ref "U1") (pin "70") (pinfunction "P5.3/XT2OUT_70") (pintype "bidirectional"))
      (node (ref "Y1") (pin "2") (pinfunction "2_2") (pintype "passive"))
    )
    (net (code "76") (name "unconnected-(JP4-Pad3)") (class "Default")
      (node (ref "JP4") (pin "3") (pinfunction "3_3") (pintype "bidirectional"))
    )
    (net (code "77") (name "unconnected-(JP4-Pad5)") (class "Default")
      (node (ref "JP4") (pin "5") (pinfunction "5_5") (pintype "bidirectional"))
    )
    (net (code "78") (name "unconnected-(JP4-Pad6)") (class "Default")
      (node (ref "JP4") (pin "6") (pinfunction "6_6") (pintype "bidirectional"))
    )
    (net (code "79") (name "unconnected-(JP4-Pad8)") (class "Default")
      (node (ref "JP4") (pin "8") (pinfunction "8_8") (pintype "bidirectional"))
    )
    (net (code "80") (name "unconnected-(JP4-Pad10)") (class "Default")
      (node (ref "JP4") (pin "10") (pinfunction "10_10") (pintype "bidirectional"))
    )
    (net (code "81") (name "unconnected-(JP4-Pad11)") (class "Default")
      (node (ref "JP4") (pin "11") (pinfunction "11_11") (pintype "bidirectional"))
    )
    (net (code "82") (name "unconnected-(JP4-Pad12)") (class "Default")
      (node (ref "JP4") (pin "12") (pinfunction "12_12") (pintype "bidirectional"))
    )
    (net (code "83") (name "unconnected-(JP4-Pad13)") (class "Default")
      (node (ref "JP4") (pin "13") (pinfunction "13_13") (pintype "bidirectional"))
    )
    (net (code "84") (name "unconnected-(JP4-Pad14)") (class "Default")
      (node (ref "JP4") (pin "14") (pinfunction "14_14") (pintype "bidirectional"))
    )
    (net (code "85") (name "unconnected-(JP5-CTS-PadP$5)") (class "Default")
      (node (ref "JP5") (pin "P$5") (pinfunction "CTS_P$5") (pintype "bidirectional"))
    )
    (net (code "86") (name "unconnected-(JP5-DTR-PadP$1)") (class "Default")
      (node (ref "JP5") (pin "P$1") (pinfunction "DTR_P$1") (pintype "bidirectional"))
    )
    (net (code "87") (name "unconnected-(U1-P1.3{slash}TA0.2-Pad24)") (class "Default")
      (node (ref "U1") (pin "24") (pinfunction "P1.3/TA0.2_24") (pintype "bidirectional"))
    )
    (net (code "88") (name "unconnected-(U1-P1.4{slash}TA0.3-Pad25)") (class "Default")
      (node (ref "U1") (pin "25") (pinfunction "P1.4/TA0.3_25") (pintype "bidirectional"))
    )
    (net (code "89") (name "unconnected-(U1-P1.5{slash}TA0.4-Pad26)") (class "Default")
      (node (ref "U1") (pin "26") (pinfunction "P1.5/TA0.4_26") (pintype "bidirectional"))
    )
    (net (code "90") (name "unconnected-(U1-P1.6{slash}TA1CLK{slash}CBOUT-Pad27)") (class "Default")
      (node (ref "U1") (pin "27") (pinfunction "P1.6/TA1CLK/CBOUT_27") (pintype "bidirectional"))
    )
    (net (code "91") (name "unconnected-(U1-P1.7{slash}TA1.0-Pad28)") (class "Default")
      (node (ref "U1") (pin "28") (pinfunction "P1.7/TA1.0_28") (pintype "bidirectional"))
    )
    (net (code "92") (name "unconnected-(U1-P2.0{slash}TA1.1-Pad29)") (class "Default")
      (node (ref "U1") (pin "29") (pinfunction "P2.0/TA1.1_29") (pintype "bidirectional"))
    )
    (net (code "93") (name "unconnected-(U1-P2.1{slash}TA1.2-Pad30)") (class "Default")
      (node (ref "U1") (pin "30") (pinfunction "P2.1/TA1.2_30") (pintype "bidirectional"))
    )
    (net (code "94") (name "unconnected-(U1-P3.5{slash}TB0.5-Pad42)") (class "Default")
      (node (ref "U1") (pin "42") (pinfunction "P3.5/TB0.5_42") (pintype "bidirectional"))
    )
    (net (code "95") (name "unconnected-(U1-P3.6{slash}TB0.6-Pad43)") (class "Default")
      (node (ref "U1") (pin "43") (pinfunction "P3.6/TB0.6_43") (pintype "bidirectional"))
    )
    (net (code "96") (name "unconnected-(U1-P4.6{slash}PM_NONE-Pad53)") (class "Default")
      (node (ref "U1") (pin "53") (pinfunction "P4.6/PM_NONE_53") (pintype "bidirectional"))
    )
    (net (code "97") (name "unconnected-(U1-P5.4{slash}XIN-Pad12)") (class "Default")
      (node (ref "U1") (pin "12") (pinfunction "P5.4/XIN_12") (pintype "bidirectional"))
    )
    (net (code "98") (name "unconnected-(U1-P5.5{slash}XOUT-Pad13)") (class "Default")
      (node (ref "U1") (pin "13") (pinfunction "P5.5/XOUT_13") (pintype "bidirectional"))
    )
    (net (code "99") (name "unconnected-(U1-P6.0{slash}CB0{slash}A0-Pad77)") (class "Default")
      (node (ref "U1") (pin "77") (pinfunction "P6.0/CB0/A0_77") (pintype "bidirectional"))
    )
    (net (code "100") (name "unconnected-(U1-P6.1{slash}CB1{slash}A1-Pad78)") (class "Default")
      (node (ref "U1") (pin "78") (pinfunction "P6.1/CB1/A1_78") (pintype "bidirectional"))
    )
    (net (code "101") (name "unconnected-(U1-P6.2{slash}CB2{slash}A2-Pad79)") (class "Default")
      (node (ref "U1") (pin "79") (pinfunction "P6.2/CB2/A2_79") (pintype "bidirectional"))
    )
    (net (code "102") (name "unconnected-(U1-P7.1{slash}CB9{slash}A13-Pad6)") (class "Default")
      (node (ref "U1") (pin "6") (pinfunction "P7.1/CB9/A13_6") (pintype "bidirectional"))
    )
    (net (code "103") (name "unconnected-(U1-P7.2{slash}CB10{slash}A14-Pad7)") (class "Default")
      (node (ref "U1") (pin "7") (pinfunction "P7.2/CB10/A14_7") (pintype "bidirectional"))
    )
    (net (code "104") (name "unconnected-(U1-P7.3{slash}CB11{slash}A15-Pad8)") (class "Default")
      (node (ref "U1") (pin "8") (pinfunction "P7.3/CB11/A15_8") (pintype "bidirectional"))
    )
    (net (code "105") (name "unconnected-(U1-P7.4{slash}TB0.2-Pad57)") (class "Default")
      (node (ref "U1") (pin "57") (pinfunction "P7.4/TB0.2_57") (pintype "bidirectional"))
    )
    (net (code "106") (name "unconnected-(U1-P7.5{slash}TB0.3-Pad58)") (class "Default")
      (node (ref "U1") (pin "58") (pinfunction "P7.5/TB0.3_58") (pintype "bidirectional"))
    )
    (net (code "107") (name "unconnected-(U1-P7.6{slash}TB0.4-Pad59)") (class "Default")
      (node (ref "U1") (pin "59") (pinfunction "P7.6/TB0.4_59") (pintype "bidirectional"))
    )
    (net (code "108") (name "unconnected-(U1-P8.0-Pad15)") (class "Default")
      (node (ref "U1") (pin "15") (pinfunction "P8.0_15") (pintype "bidirectional"))
    )
    (net (code "109") (name "unconnected-(U1-P8.1-Pad16)") (class "Default")
      (node (ref "U1") (pin "16") (pinfunction "P8.1_16") (pintype "bidirectional"))
    )
    (net (code "110") (name "unconnected-(U1-P8.2-Pad17)") (class "Default")
      (node (ref "U1") (pin "17") (pinfunction "P8.2_17") (pintype "bidirectional"))
    )
    (net (code "111") (name "unconnected-(U1-PJ.0{slash}TDO-Pad72)") (class "Default")
      (node (ref "U1") (pin "72") (pinfunction "PJ.0/TDO_72") (pintype "bidirectional"))
    )
    (net (code "112") (name "unconnected-(U1-PJ.1{slash}TDI{slash}TCK-Pad73)") (class "Default")
      (node (ref "U1") (pin "73") (pinfunction "PJ.1/TDI/TCK_73") (pintype "bidirectional"))
    )
    (net (code "113") (name "unconnected-(U1-PJ.2{slash}TMS-Pad74)") (class "Default")
      (node (ref "U1") (pin "74") (pinfunction "PJ.2/TMS_74") (pintype "bidirectional"))
    )
    (net (code "114") (name "unconnected-(U1-PJ.3{slash}TCK-Pad75)") (class "Default")
      (node (ref "U1") (pin "75") (pinfunction "PJ.3/TCK_75") (pintype "bidirectional"))
    )
    (net (code "115") (name "unconnected-(U1-PU.0{slash}DP-Pad62)") (class "Default")
      (node (ref "U1") (pin "62") (pinfunction "PU.0/DP_62") (pintype "bidirectional"))
    )
    (net (code "116") (name "unconnected-(U1-PU.1{slash}DM-Pad64)") (class "Default")
      (node (ref "U1") (pin "64") (pinfunction "PU.1/DM_64") (pintype "bidirectional"))
    )
    (net (code "117") (name "unconnected-(U1-VBUS-Pad65)") (class "Default")
      (node (ref "U1") (pin "65") (pinfunction "VBUS_65") (pintype "bidirectional"))
    )
    (net (code "118") (name "unconnected-(XB1-AD0{slash}DIO0-Pad20)") (class "Default")
      (node (ref "XB1") (pin "20") (pinfunction "AD0/DIO0_20") (pintype "bidirectional"))
    )
    (net (code "119") (name "unconnected-(XB1-AD1{slash}DIO1-Pad19)") (class "Default")
      (node (ref "XB1") (pin "19") (pinfunction "AD1/DIO1_19") (pintype "bidirectional"))
    )
    (net (code "120") (name "unconnected-(XB1-AD2{slash}DIO2-Pad18)") (class "Default")
      (node (ref "XB1") (pin "18") (pinfunction "AD2/DIO2_18") (pintype "bidirectional"))
    )
    (net (code "121") (name "unconnected-(XB1-ASSOC{slash}AD5{slash}DIO5-Pad15)") (class "Default")
      (node (ref "XB1") (pin "15") (pinfunction "ASSOC/AD5/DIO5_15") (pintype "bidirectional"))
    )
    (net (code "122") (name "unconnected-(XB1-CD{slash}DOUT_EN{slash}DO8-Pad4)") (class "Default")
      (node (ref "XB1") (pin "4") (pinfunction "CD/DOUT_EN/DO8_4") (pintype "output"))
    )
    (net (code "123") (name "unconnected-(XB1-COORD_SEL{slash}AD3{slash}DIO3-Pad17)") (class "Default")
      (node (ref "XB1") (pin "17") (pinfunction "COORD_SEL/AD3/DIO3_17") (pintype "bidirectional"))
    )
    (net (code "124") (name "unconnected-(XB1-ON{slash}~{SLEEP}-Pad13)") (class "Default")
      (node (ref "XB1") (pin "13") (pinfunction "ON/~{SLEEP}_13") (pintype "output"))
    )
    (net (code "125") (name "unconnected-(XB1-PWM0{slash}RSSI-Pad6)") (class "Default")
      (node (ref "XB1") (pin "6") (pinfunction "PWM0/RSSI_6") (pintype "output"))
    )
    (net (code "126") (name "unconnected-(XB1-RF_TX{slash}AD4{slash}DIO4-Pad11)") (class "Default")
      (node (ref "XB1") (pin "11") (pinfunction "RF_TX/AD4/DIO4_11") (pintype "bidirectional"))
    )
    (net (code "127") (name "unconnected-(XB1-VREF-Pad14)") (class "Default")
      (node (ref "XB1") (pin "14") (pinfunction "VREF_14") (pintype "input"))
    )
    (net (code "128") (name "unconnected-(XB1-~{CTS}{slash}DIO7-Pad12)") (class "Default")
      (node (ref "XB1") (pin "12") (pinfunction "~{CTS}/DIO7_12") (pintype "bidirectional"))
    )
    (net (code "129") (name "unconnected-(XB1-~{DTR}{slash}SLEEP_RQ{slash}DI8-Pad9)") (class "Default")
      (node (ref "XB1") (pin "9") (pinfunction "~{DTR}/SLEEP_RQ/DI8_9") (pintype "bidirectional"))
    )
    (net (code "130") (name "unconnected-(XB1-~{RESET}-Pad5)") (class "Default")
      (node (ref "XB1") (pin "5") (pinfunction "~{RESET}_5") (pintype "input"))
    )
    (net (code "131") (name "unconnected-(XB1-~{RTS}{slash}AD6{slash}DIO6-Pad16)") (class "Default")
      (node (ref "XB1") (pin "16") (pinfunction "~{RTS}/AD6/DIO6_16") (pintype "bidirectional"))
    )
  )
)
